# etna-sch-ui.net
KiCad netlist of a schematic drawn in Altium Designer
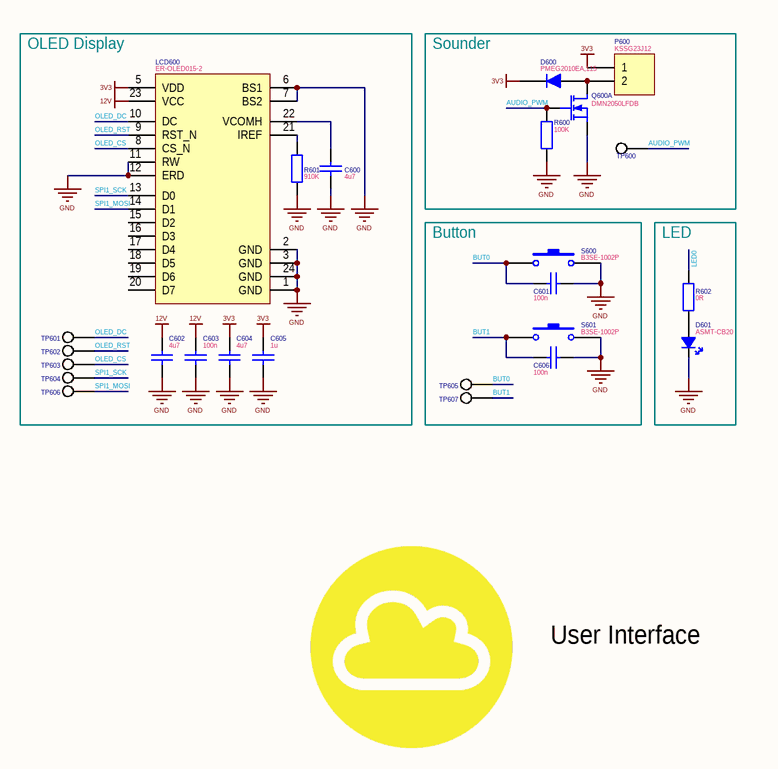
[diagram p0: etna-sch-ui.SchDoc]

(export (version "E")
  (design (tool "Eeschema 10.0.6"))
  (components
    (comp (ref "C600")
      (value "4u7")
      (footprint "0603-capacitor")
      (description "Capacitor")
      (libsource (lib "illysky-components") (part "CAP"))
    )
    (comp (ref "C601")
      (value "100n")
      (footprint "0402-capacitor")
      (description "Capacitor")
      (libsource (lib "illysky-components") (part "CAP"))
    )
    (comp (ref "C602")
      (value "4u7")
      (footprint "0603-capacitor")
      (description "Capacitor")
      (libsource (lib "illysky-components") (part "CAP"))
    )
    (comp (ref "C603")
      (value "100n")
      (footprint "0603-capacitor")
      (description "Capacitor")
      (libsource (lib "illysky-components") (part "CAP"))
    )
    (comp (ref "C604")
      (value "4u7")
      (footprint "0603-capacitor")
      (description "Capacitor")
      (libsource (lib "illysky-components") (part "CAP"))
    )
    (comp (ref "C605")
      (value "1u")
      (footprint "0603-capacitor")
      (description "Capacitor")
      (libsource (lib "illysky-components") (part "CAP"))
    )
    (comp (ref "C606")
      (value "100n")
      (footprint "0402-capacitor")
      (description "Capacitor")
      (libsource (lib "illysky-components") (part "CAP"))
    )
    (comp (ref "D600")
      (value "PMEG2010EA,115")
      (footprint "SOD-323")
      (description "Diode")
      (fields (field (name "PUBLISHER") "Altium Limited"))
      (libsource (lib "illysky-components") (part "DIODE"))
    )
    (comp (ref "D601")
      (value "ASMT-CB20")
      (footprint "0603-LED")
      (description "LED")
      (fields (field (name "PUBLISHER") "Altium Limited"))
      (libsource (lib "illysky-components") (part "LED"))
    )
    (comp (ref "LCD600")
      (value "ER-OLED015-2")
      (footprint "XF2M-2415-1A-REV")
      (description "I2C 1.5\"OLED Display Serial 128x64 Module,SSD1309,White on Black")
      (libsource (lib "illysky-components") (part "ER-OLED015-2"))
    )
    (comp (ref "P600")
      (value "KSSG23J12")
      (footprint "KSSG23J12")
      (description "Header, 2-Pin")
      (fields (field (name "PUBLISHER") "Altium Limited"))
      (libsource (lib "Miscellaneous Connectors") (part "Header 2"))
    )
    (comp (ref "Q600")
      (value "DMN2050LFDB")
      (footprint "U-DFN2020-6")
      (description "20 V, 800 mA dual N-channel Trench MOSFET")
      (libsource (lib "illysky-components") (part "DMN2050LFDB"))
    )
    (comp (ref "R600")
      (value "100K")
      (footprint "0402-resistor")
      (description "Resistor")
      (libsource (lib "altium-import") (part "root_1_RES_"))
    )
    (comp (ref "R601")
      (value "910K")
      (footprint "0402-resistor")
      (description "Resistor")
      (libsource (lib "altium-import") (part "root_1_RES_"))
    )
    (comp (ref "R602")
      (value "0R")
      (footprint "0402-resistor")
      (description "Resistor")
      (libsource (lib "altium-import") (part "root_1_RES_"))
    )
    (comp (ref "S600")
      (value "B3SE-1002P")
      (footprint "B3SE-1002P")
      (description "Switch")
      (fields (field (name "PUBLISHER") "Altium Limited"))
      (libsource (lib "Miscellaneous Devices") (part "SW-PB"))
    )
    (comp (ref "S601")
      (value "B3SE-1002P")
      (footprint "B3SE-1002P")
      (description "Switch")
      (fields (field (name "PUBLISHER") "Altium Limited"))
      (libsource (lib "Miscellaneous Devices") (part "SW-PB"))
    )
    (comp (ref "TP600")
      (value "TP")
      (footprint "TESTPOINT")
      (libsource (lib "illysky-components") (part "TEST_POINT"))
    )
    (comp (ref "TP601")
      (value "TP")
      (footprint "TESTPOINT")
      (libsource (lib "illysky-components") (part "TEST_POINT"))
    )
    (comp (ref "TP602")
      (value "TP")
      (footprint "TESTPOINT")
      (libsource (lib "illysky-components") (part "TEST_POINT"))
    )
    (comp (ref "TP603")
      (value "TP")
      (footprint "TESTPOINT")
      (libsource (lib "illysky-components") (part "TEST_POINT"))
    )
    (comp (ref "TP604")
      (value "TP")
      (footprint "TESTPOINT")
      (libsource (lib "illysky-components") (part "TEST_POINT"))
    )
    (comp (ref "TP605")
      (value "TP")
      (footprint "TESTPOINT")
      (libsource (lib "illysky-components") (part "TEST_POINT"))
    )
    (comp (ref "TP606")
      (value "TP")
      (footprint "TESTPOINT")
      (libsource (lib "illysky-components") (part "TEST_POINT"))
    )
    (comp (ref "TP607")
      (value "TP")
      (footprint "TESTPOINT")
      (libsource (lib "illysky-components") (part "TEST_POINT"))
    )
  )
  (nets
    (net (code "1") (name "/AUDIO_PWM") (class "Default")
      (node (ref "Q600") (pin "G1") (pinfunction "G1_G1") (pintype "passive"))
      (node (ref "R600") (pin "2") (pinfunction "2_2") (pintype "passive"))
      (node (ref "TP600") (pin "1") (pinfunction "GND_1") (pintype "passive"))
    )
    (net (code "2") (name "/BUT0") (class "Default")
      (node (ref "C601") (pin "2") (pinfunction "2_2") (pintype "passive"))
      (node (ref "S600") (pin "2") (pinfunction "2_2") (pintype "passive"))
      (node (ref "TP605") (pin "1") (pinfunction "GND_1") (pintype "passive"))
    )
    (net (code "3") (name "/BUT1") (class "Default")
      (node (ref "C606") (pin "2") (pinfunction "2_2") (pintype "passive"))
      (node (ref "S601") (pin "2") (pinfunction "2_2") (pintype "passive"))
      (node (ref "TP607") (pin "1") (pinfunction "GND_1") (pintype "passive"))
    )
    (net (code "4") (name "/LED0") (class "Default")
      (node (ref "R602") (pin "2") (pinfunction "2_2") (pintype "passive"))
    )
    (net (code "5") (name "/OLED_CS") (class "Default")
      (node (ref "LCD600") (pin "8") (pinfunction "CS_N_8") (pintype "passive"))
      (node (ref "TP603") (pin "1") (pinfunction "GND_1") (pintype "passive"))
    )
    (net (code "6") (name "/OLED_DC") (class "Default")
      (node (ref "LCD600") (pin "10") (pinfunction "DC_10") (pintype "passive"))
      (node (ref "TP601") (pin "1") (pinfunction "GND_1") (pintype "passive"))
    )
    (net (code "7") (name "/OLED_RST") (class "Default")
      (node (ref "LCD600") (pin "9") (pinfunction "RST_N_9") (pintype "passive"))
      (node (ref "TP602") (pin "1") (pinfunction "GND_1") (pintype "passive"))
    )
    (net (code "8") (name "/SPI1_MOSI") (class "Default")
      (node (ref "LCD600") (pin "14") (pinfunction "D1_14") (pintype "passive"))
      (node (ref "TP606") (pin "1") (pinfunction "GND_1") (pintype "passive"))
    )
    (net (code "9") (name "/SPI1_SCK") (class "Default")
      (node (ref "LCD600") (pin "13") (pinfunction "D0_13") (pintype "passive"))
      (node (ref "TP604") (pin "1") (pinfunction "GND_1") (pintype "passive"))
    )
    (net (code "10") (name "3V3") (class "Default")
      (node (ref "C604") (pin "1") (pinfunction "1_1") (pintype "passive"))
      (node (ref "C605") (pin "1") (pinfunction "1_1") (pintype "passive"))
      (node (ref "D600") (pin "2") (pinfunction "K_2") (pintype "passive"))
      (node (ref "LCD600") (pin "5") (pinfunction "VDD_5") (pintype "passive"))
      (node (ref "P600") (pin "1") (pinfunction "1_1") (pintype "passive"))
    )
    (net (code "11") (name "12V") (class "Default")
      (node (ref "C602") (pin "1") (pinfunction "1_1") (pintype "passive"))
      (node (ref "C603") (pin "1") (pinfunction "1_1") (pintype "passive"))
      (node (ref "LCD600") (pin "23") (pinfunction "VCC_23") (pintype "passive"))
    )
    (net (code "12") (name "GND") (class "Default")
      (node (ref "C600") (pin "2") (pinfunction "2_2") (pintype "passive"))
      (node (ref "C601") (pin "1") (pinfunction "1_1") (pintype "passive"))
      (node (ref "C602") (pin "2") (pinfunction "2_2") (pintype "passive"))
      (node (ref "C603") (pin "2") (pinfunction "2_2") (pintype "passive"))
      (node (ref "C604") (pin "2") (pinfunction "2_2") (pintype "passive"))
      (node (ref "C605") (pin "2") (pinfunction "2_2") (pintype "passive"))
      (node (ref "C606") (pin "1") (pinfunction "1_1") (pintype "passive"))
      (node (ref "D601") (pin "2") (pinfunction "K_2") (pintype "passive"))
      (node (ref "LCD600") (pin "1") (pinfunction "GND_1") (pintype "passive"))
      (node (ref "LCD600") (pin "11") (pinfunction "RW_11") (pintype "passive"))
      (node (ref "LCD600") (pin "12") (pinfunction "ERD_12") (pintype "passive"))
      (node (ref "LCD600") (pin "2") (pinfunction "GND_2") (pintype "passive"))
      (node (ref "LCD600") (pin "24") (pinfunction "GND_24") (pintype "passive"))
      (node (ref "LCD600") (pin "3") (pinfunction "GND_3") (pintype "passive"))
      (node (ref "LCD600") (pin "6") (pinfunction "BS1_6") (pintype "passive"))
      (node (ref "LCD600") (pin "7") (pinfunction "BS2_7") (pintype "passive"))
      (node (ref "Q600") (pin "S1") (pinfunction "S1_S1") (pintype "passive"))
      (node (ref "R600") (pin "1") (pinfunction "1_1") (pintype "passive"))
      (node (ref "R601") (pin "1") (pinfunction "1_1") (pintype "passive"))
      (node (ref "S600") (pin "1") (pinfunction "1_1") (pintype "passive"))
      (node (ref "S601") (pin "1") (pinfunction "1_1") (pintype "passive"))
    )
    (net (code "13") (name "Net-(D600-A)") (class "Default")
      (node (ref "D600") (pin "1") (pinfunction "A_1") (pintype "passive"))
      (node (ref "P600") (pin "2") (pinfunction "2_2") (pintype "passive"))
      (node (ref "Q600") (pin "D1") (pinfunction "D1_D1") (pintype "passive"))
    )
    (net (code "14") (name "Net-(D601-A)") (class "Default")
      (node (ref "D601") (pin "1") (pinfunction "A_1") (pintype "passive"))
      (node (ref "R602") (pin "1") (pinfunction "1_1") (pintype "passive"))
    )
    (net (code "15") (name "Net-(LCD600-IREF)") (class "Default")
      (node (ref "LCD600") (pin "21") (pinfunction "IREF_21") (pintype "passive"))
      (node (ref "R601") (pin "2") (pinfunction "2_2") (pintype "passive"))
    )
    (net (code "16") (name "Net-(LCD600-VCOMH)") (class "Default")
      (node (ref "C600") (pin "1") (pinfunction "1_1") (pintype "passive"))
      (node (ref "LCD600") (pin "22") (pinfunction "VCOMH_22") (pintype "passive"))
    )
    (net (code "17") (name "unconnected-(LCD600-D2-Pad15)") (class "Default")
      (node (ref "LCD600") (pin "15") (pinfunction "D2_15") (pintype "passive"))
    )
    (net (code "18") (name "unconnected-(LCD600-D3-Pad16)") (class "Default")
      (node (ref "LCD600") (pin "16") (pinfunction "D3_16") (pintype "passive"))
    )
    (net (code "19") (name "unconnected-(LCD600-D4-Pad17)") (class "Default")
      (node (ref "LCD600") (pin "17") (pinfunction "D4_17") (pintype "passive"))
    )
    (net (code "20") (name "unconnected-(LCD600-D5-Pad18)") (class "Default")
      (node (ref "LCD600") (pin "18") (pinfunction "D5_18") (pintype "passive"))
    )
    (net (code "21") (name "unconnected-(LCD600-D6-Pad19)") (class "Default")
      (node (ref "LCD600") (pin "19") (pinfunction "D6_19") (pintype "passive"))
    )
    (net (code "22") (name "unconnected-(LCD600-D7-Pad20)") (class "Default")
      (node (ref "LCD600") (pin "20") (pinfunction "D7_20") (pintype "passive"))
    )
    (net (code "23") (name "unconnected-(LCD600-NC-Pad4)") (class "Default")
      (node (ref "LCD600") (pin "4") (pinfunction "NC_4") (pintype "passive"))
    )
  )
)
